# power_schem.net
KiCad netlist of a schematic drawn in Altium Designer
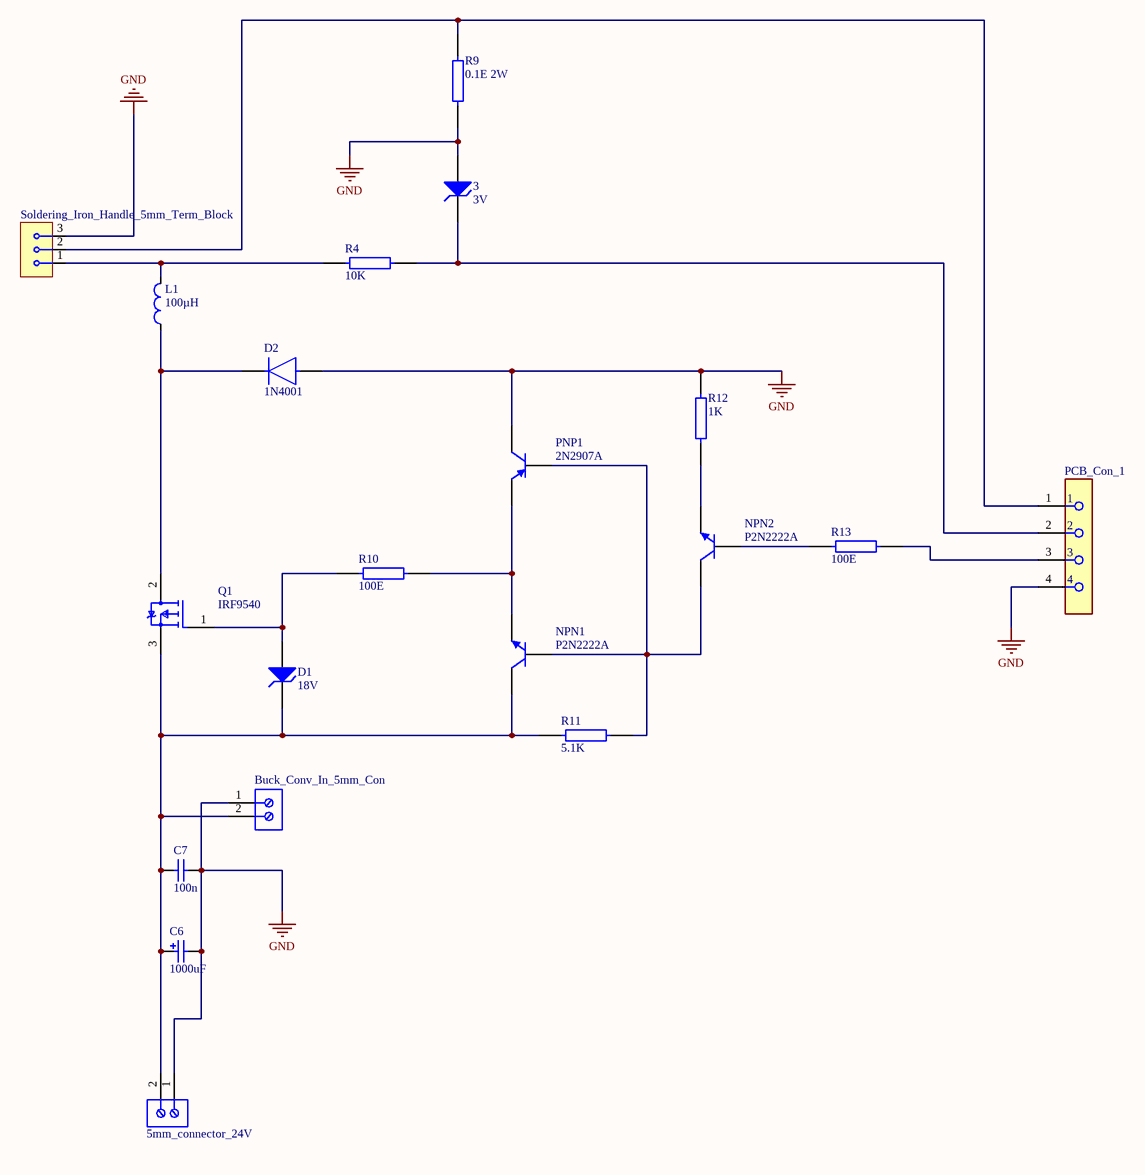
[diagram p0: power_schem.SchDoc]

(export (version "E")
  (design (tool "Eeschema 10.0.6"))
  (components
    (comp (ref "3")
      (value "3V")
      (footprint "Zener_Diode")
      (fields (field (name "PARTNUMBER") "1N5931BRLG") (field (name "MANUFACTURER") "On Semiconductor"))
      (libsource (lib "library1") (part "Zener_Diode"))
    )
    (comp (ref "5mm_connector_24V")
      (value "~")
      (footprint "screw_terminal")
      (fields (field (name "VOLTAGE") "300V"))
      (libsource (lib "library1") (part "Screw_Terminal"))
    )
    (comp (ref "Buck_Conv_In_5mm_Con")
      (value "~")
      (footprint "screw_terminal")
      (fields (field (name "VOLTAGE") "300V"))
      (libsource (lib "library1") (part "Screw_Terminal"))
    )
    (comp (ref "C6")
      (value "1000uF")
      (footprint "Capacitor_Polarised")
      (fields (field (name "TOLERANCE") "10%") (field (name "MANUFACTURER") "Murata"))
      (libsource (lib "library1") (part "Capacitor_Polarised"))
    )
    (comp (ref "C7")
      (value "100n")
      (footprint "Capacitor_Monolitoc")
      (fields (field (name "TOLERANCE") "10%") (field (name "MANUFACTURER") "Murata"))
      (libsource (lib "library1") (part "Capacitor_Monolitic"))
    )
    (comp (ref "D1")
      (value "18V")
      (footprint "Zener_Diode")
      (fields (field (name "PARTNUMBER") "1N5931BRLG") (field (name "MANUFACTURER") "On Semiconductor"))
      (libsource (lib "library1") (part "Zener_Diode"))
    )
    (comp (ref "D2")
      (value "1N4001")
      (footprint "Zener_Diode")
      (libsource (lib "library1") (part "Diode_UF5408"))
    )
    (comp (ref "L1")
      (value "100µH")
      (footprint "Coil")
      (fields (field (name "TOLERANCE") "20%"))
      (libsource (lib "library1") (part "100µH_Inductor"))
    )
    (comp (ref "NPN1")
      (value "P2N2222A")
      (footprint "NPN_Transistor_2N2222A")
      (fields (field (name "PARTNUMBER") "P2N2222AG") (field (name "MANUFACTURER") "On Semiconductor"))
      (libsource (lib "library1") (part "NPN_Transistor_2N2222A"))
    )
    (comp (ref "NPN2")
      (value "P2N2222A")
      (footprint "NPN_Transistor_2N2222A")
      (fields (field (name "PARTNUMBER") "P2N2222AG") (field (name "MANUFACTURER") "On Semiconductor"))
      (libsource (lib "library1") (part "NPN_Transistor_2N2222A"))
    )
    (comp (ref "PCB_Con_1")
      (value "~")
      (footprint "Header-Female-JST_4pin")
      (libsource (lib "library1") (part "Header-Female-JST_4pin"))
    )
    (comp (ref "PNP1")
      (value "2N2907A")
      (footprint "PNP_Transistor_2N2907A")
      (fields (field (name "MANUFACTURER") "On Semiconductor") (field (name "PARTNUMBER") "MPSA92G"))
      (libsource (lib "library1") (part "PNP_Transistor_2N2907A"))
    )
    (comp (ref "Q1")
      (value "IRF9540")
      (footprint "Mosfet_IRF9540NPBF")
      (libsource (lib "library1") (part "Mosfet_IRF9540NPBF"))
    )
    (comp (ref "R4")
      (value "10K")
      (footprint "Resistor")
      (fields (field (name "TOLERANCE") "1%"))
      (libsource (lib "library1") (part "Resistor"))
    )
    (comp (ref "R9")
      (value "0.1E 2W")
      (footprint "Resistor")
      (fields (field (name "TOLERANCE") "1%"))
      (libsource (lib "library1") (part "Resistor"))
    )
    (comp (ref "R10")
      (value "100E")
      (footprint "Resistor")
      (fields (field (name "TOLERANCE") "1%"))
      (libsource (lib "library1") (part "Resistor"))
    )
    (comp (ref "R11")
      (value "5.1K")
      (footprint "Resistor")
      (fields (field (name "TOLERANCE") "1%"))
      (libsource (lib "library1") (part "Resistor"))
    )
    (comp (ref "R12")
      (value "1K")
      (footprint "Resistor")
      (fields (field (name "TOLERANCE") "1%"))
      (libsource (lib "library1") (part "Resistor"))
    )
    (comp (ref "R13")
      (value "100E")
      (footprint "Resistor")
      (fields (field (name "TOLERANCE") "1%"))
      (libsource (lib "library1") (part "Resistor"))
    )
    (comp (ref "Soldering_Iron_Handle_5mm_Term_Block")
      (value "~")
      (footprint "3Pin_Connector")
      (libsource (lib "library1") (part "3Pin_Connector"))
    )
  )
  (nets
    (net (code "1") (name "GND") (class "Default")
      (node (ref "3") (pin "2") (pinfunction "A_2") (pintype "passive"))
      (node (ref "5mm_connector_24V") (pin "1") (pinfunction "1_1") (pintype "passive"))
      (node (ref "Buck_Conv_In_5mm_Con") (pin "1") (pinfunction "1_1") (pintype "passive"))
      (node (ref "C6") (pin "2") (pinfunction "2_2") (pintype "passive"))
      (node (ref "C7") (pin "2") (pinfunction "2_2") (pintype "passive"))
      (node (ref "D2") (pin "2") (pinfunction "A_2") (pintype "passive"))
      (node (ref "PCB_Con_1") (pin "4") (pinfunction "4_4") (pintype "passive"))
      (node (ref "PNP1") (pin "3") (pinfunction "C_3") (pintype "passive"))
      (node (ref "R12") (pin "2") (pinfunction "2_2") (pintype "passive"))
      (node (ref "R9") (pin "1") (pinfunction "1_1") (pintype "passive"))
      (node (ref "Soldering_Iron_Handle_5mm_Term_Block") (pin "3") (pintype "passive"))
    )
    (net (code "2") (name "Net-(3-K)") (class "Default")
      (node (ref "3") (pin "1") (pinfunction "K_1") (pintype "passive"))
      (node (ref "PCB_Con_1") (pin "2") (pinfunction "2_2") (pintype "passive"))
      (node (ref "R4") (pin "2") (pinfunction "2_2") (pintype "passive"))
    )
    (net (code "3") (name "Net-(D1-A)") (class "Default")
      (node (ref "D1") (pin "2") (pinfunction "A_2") (pintype "passive"))
      (node (ref "Q1") (pin "1") (pinfunction "G_1") (pintype "passive"))
      (node (ref "R10") (pin "1") (pinfunction "1_1") (pintype "passive"))
    )
    (net (code "4") (name "Net-(D1-K)") (class "Default")
      (node (ref "5mm_connector_24V") (pin "2") (pinfunction "2_2") (pintype "passive"))
      (node (ref "Buck_Conv_In_5mm_Con") (pin "2") (pinfunction "2_2") (pintype "passive"))
      (node (ref "C6") (pin "1") (pinfunction "1_1") (pintype "passive"))
      (node (ref "C7") (pin "1") (pinfunction "1_1") (pintype "passive"))
      (node (ref "D1") (pin "1") (pinfunction "K_1") (pintype "passive"))
      (node (ref "NPN1") (pin "1") (pinfunction "C_1") (pintype "passive"))
      (node (ref "Q1") (pin "3") (pinfunction "S_3") (pintype "passive"))
      (node (ref "R11") (pin "1") (pinfunction "1_1") (pintype "passive"))
    )
    (net (code "5") (name "Net-(D2-C)") (class "Default")
      (node (ref "D2") (pin "1") (pinfunction "C_1") (pintype "passive"))
      (node (ref "L1") (pin "1") (pinfunction "1_1") (pintype "passive"))
      (node (ref "Q1") (pin "2") (pinfunction "D_2") (pintype "passive"))
    )
    (net (code "6") (name "Net-(L1-Pad2)") (class "Default")
      (node (ref "L1") (pin "2") (pinfunction "2_2") (pintype "passive"))
      (node (ref "R4") (pin "1") (pinfunction "1_1") (pintype "passive"))
      (node (ref "Soldering_Iron_Handle_5mm_Term_Block") (pin "1") (pinfunction "1_1") (pintype "passive"))
    )
    (net (code "7") (name "Net-(NPN1-B)") (class "Default")
      (node (ref "NPN1") (pin "2") (pinfunction "B_2") (pintype "passive"))
      (node (ref "NPN2") (pin "1") (pinfunction "C_1") (pintype "passive"))
      (node (ref "PNP1") (pin "2") (pinfunction "B_2") (pintype "passive"))
      (node (ref "R11") (pin "2") (pinfunction "2_2") (pintype "passive"))
    )
    (net (code "8") (name "Net-(NPN1-E)") (class "Default")
      (node (ref "NPN1") (pin "3") (pinfunction "E_3") (pintype "passive"))
      (node (ref "PNP1") (pin "1") (pinfunction "E_1") (pintype "passive"))
      (node (ref "R10") (pin "2") (pinfunction "2_2") (pintype "passive"))
    )
    (net (code "9") (name "Net-(NPN2-B)") (class "Default")
      (node (ref "NPN2") (pin "2") (pinfunction "B_2") (pintype "passive"))
      (node (ref "R13") (pin "2") (pinfunction "2_2") (pintype "passive"))
    )
    (net (code "10") (name "Net-(NPN2-E)") (class "Default")
      (node (ref "NPN2") (pin "3") (pinfunction "E_3") (pintype "passive"))
      (node (ref "R12") (pin "1") (pinfunction "1_1") (pintype "passive"))
    )
    (net (code "11") (name "Net-(PCB_Con_1-Pad1)") (class "Default")
      (node (ref "PCB_Con_1") (pin "1") (pinfunction "1_1") (pintype "passive"))
      (node (ref "R9") (pin "2") (pinfunction "2_2") (pintype "passive"))
      (node (ref "Soldering_Iron_Handle_5mm_Term_Block") (pin "2") (pinfunction "2_2") (pintype "passive"))
    )
    (net (code "12") (name "Net-(PCB_Con_1-Pad3)") (class "Default")
      (node (ref "PCB_Con_1") (pin "3") (pinfunction "3_3") (pintype "passive"))
      (node (ref "R13") (pin "1") (pinfunction "1_1") (pintype "passive"))
    )
  )
)
